# 13_TF_schdoc.net
KiCad netlist of a schematic drawn in Altium Designer
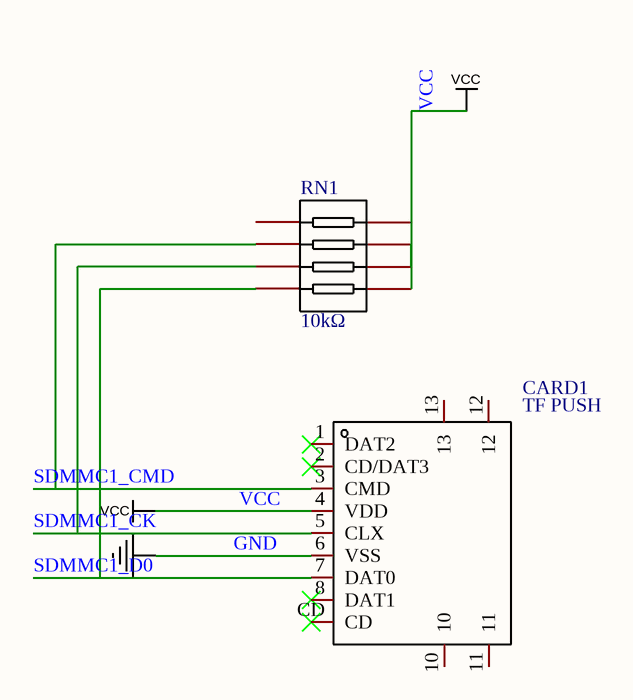
[diagram p0: 13_TF卡.schdoc.schdoc]

(export (version "E")
  (design (tool "Eeschema 10.0.6"))
  (components
    (comp (ref "CARD1")
      (value "TF PUSH")
      (description "卡类型:MicroSD卡(TF卡);连接器类型:卡座;卡连接方式:自弹式;本体最大高度:2mm;工作温度范围:-20℃~+90℃;")
      (fields (field (name "NAME") "TF PUSH") (field (name "MANUFACTURER") "SHOU HAN(首韩)"))
      (libsource (lib "altium-import") (part "root_0_TF PUSH_"))
    )
    (comp (ref "RN1")
      (value "10kΩ")
      (description "阻值:10kΩ;精度:±5%;单个元件功率:62.5mW;电阻器数:4;")
      (fields
        (field (name "NAME") "10kΩ")
        (field (name "MANUFACTURER") "YAGEO(国巨)")
        (field (name "MANUFACTURER PART") "YC164-JR-0710KL")
      )
      (libsource (lib "altium-import") (part "root_1_mirrored_YC164-JR-0710KL_"))
    )
  )
  (nets
    (net (code "1") (name "/GND") (class "Default")
      (node (ref "CARD1") (pin "6") (pinfunction "VSS_6") (pintype "passive"))
    )
    (net (code "2") (name "/SDMMC1_CK") (class "Default")
      (node (ref "CARD1") (pin "5") (pinfunction "CLX_5") (pintype "passive"))
      (node (ref "RN1") (pin "2") (pinfunction "2_2") (pintype "passive"))
    )
    (net (code "3") (name "/SDMMC1_CMD") (class "Default")
      (node (ref "CARD1") (pin "3") (pinfunction "CMD_3") (pintype "passive"))
      (node (ref "RN1") (pin "3") (pinfunction "3_3") (pintype "passive"))
    )
    (net (code "4") (name "/SDMMC1_D0") (class "Default")
      (node (ref "CARD1") (pin "7") (pinfunction "DAT0_7") (pintype "passive"))
      (node (ref "RN1") (pin "1") (pinfunction "1_1") (pintype "passive"))
    )
    (net (code "5") (name "VCC") (class "Default")
      (node (ref "CARD1") (pin "4") (pinfunction "VDD_4") (pintype "passive"))
      (node (ref "RN1") (pin "5") (pinfunction "5_5") (pintype "passive"))
      (node (ref "RN1") (pin "6") (pinfunction "6_6") (pintype "passive"))
      (node (ref "RN1") (pin "7") (pinfunction "7_7") (pintype "passive"))
      (node (ref "RN1") (pin "8") (pinfunction "8_8") (pintype "passive"))
    )
    (net (code "6") (name "unconnected-(CARD1-CD{slash}DAT3-Pad2)") (class "Default")
      (node (ref "CARD1") (pin "2") (pinfunction "CD/DAT3_2") (pintype "passive+no_connect"))
    )
    (net (code "7") (name "unconnected-(CARD1-DAT1-Pad8)") (class "Default")
      (node (ref "CARD1") (pin "8") (pinfunction "DAT1_8") (pintype "passive+no_connect"))
    )
    (net (code "8") (name "unconnected-(CARD1-DAT2-Pad1)") (class "Default")
      (node (ref "CARD1") (pin "1") (pinfunction "DAT2_1") (pintype "passive+no_connect"))
    )
    (net (code "9") (name "unconnected-(CARD1-Pad10)") (class "Default")
      (node (ref "CARD1") (pin "10") (pinfunction "10_10") (pintype "passive"))
    )
    (net (code "10") (name "unconnected-(CARD1-Pad11)") (class "Default")
      (node (ref "CARD1") (pin "11") (pinfunction "11_11") (pintype "passive"))
    )
    (net (code "11") (name "unconnected-(CARD1-Pad12)") (class "Default")
      (node (ref "CARD1") (pin "12") (pinfunction "12_12") (pintype "passive"))
    )
    (net (code "12") (name "unconnected-(CARD1-Pad13)") (class "Default")
      (node (ref "CARD1") (pin "13") (pinfunction "13_13") (pintype "passive"))
    )
    (net (code "13") (name "unconnected-(CARD1-PadCD)") (class "Default")
      (node (ref "CARD1") (pin "CD") (pinfunction "CD_CD") (pintype "passive+no_connect"))
    )
    (net (code "14") (name "unconnected-(RN1-Pad4)") (class "Default")
      (node (ref "RN1") (pin "4") (pinfunction "4_4") (pintype "passive"))
    )
  )
)
